# untitled.net
KiCad netlist of a schematic drawn in EAGLE
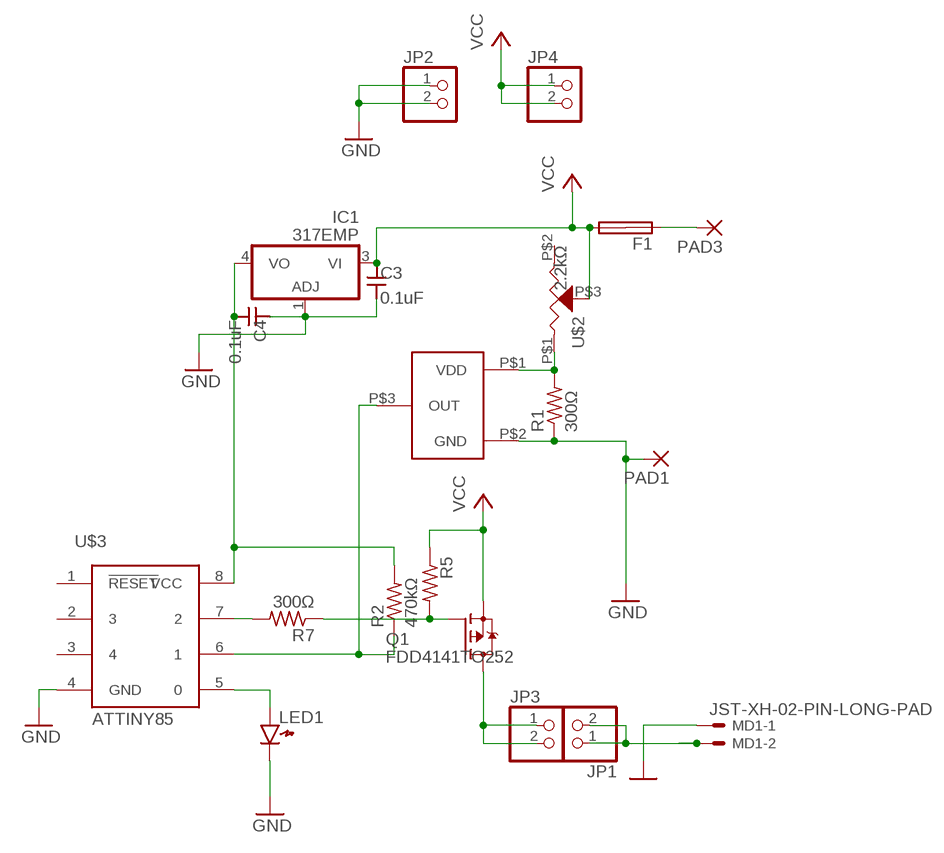
[diagram p0: schematic, sheet 1]

(export (version "E")
  (design (tool "Eeschema 10.0.6"))
  (components
    (comp (ref "C3")
      (value "0.1uF")
      (footprint "eagle-import:SMD1608")
      (libsource (lib "eagle-import") (part "CAPACITOR1608"))
    )
    (comp (ref "C4")
      (value "0.1uF")
      (footprint "eagle-import:SMD1608")
      (libsource (lib "eagle-import") (part "CAPACITOR1608"))
    )
    (comp (ref "F1")
      (value "SH32")
      (footprint "eagle-import:SH32")
      (fields (field (name "MPN") "10207101009"))
      (libsource (lib "eagle-import") (part "SH32"))
    )
    (comp (ref "IC1")
      (value "317EMP")
      (footprint "eagle-import:SOT223")
      (libsource (lib "eagle-import") (part "317EMP"))
    )
    (comp (ref "JP1")
      (value "PINHD-1X2")
      (footprint "eagle-import:1X02")
      (libsource (lib "eagle-import") (part "PINHD-1X2"))
    )
    (comp (ref "JP2")
      (value "PINHD-1X2")
      (footprint "eagle-import:1X02")
      (libsource (lib "eagle-import") (part "PINHD-1X2"))
    )
    (comp (ref "JP3")
      (value "PINHD-1X2")
      (footprint "eagle-import:1X02")
      (libsource (lib "eagle-import") (part "PINHD-1X2"))
    )
    (comp (ref "JP4")
      (value "PINHD-1X2")
      (footprint "eagle-import:1X02")
      (libsource (lib "eagle-import") (part "PINHD-1X2"))
    )
    (comp (ref "LED1")
      (value "LED1608")
      (footprint "eagle-import:LED1608")
      (libsource (lib "eagle-import") (part "LED1608"))
    )
    (comp (ref "MD1")
      (value "JST-XH-02-PIN-LONG-PAD")
      (footprint "eagle-import:JST-XH-02-PACKAGE-LONG-PAD")
      (libsource (lib "eagle-import") (part "JST-XH-02-PIN-LONG-PAD"))
    )
    (comp (ref "PAD1")
      (value "3,81/1,4")
      (footprint "eagle-import:3,81_1,4")
      (libsource (lib "eagle-import") (part "3,81/1,4"))
    )
    (comp (ref "PAD3")
      (value "3,81/1,4")
      (footprint "eagle-import:3,81_1,4")
      (libsource (lib "eagle-import") (part "3,81/1,4"))
    )
    (comp (ref "Q1")
      (value "FDD4141TO252")
      (footprint "eagle-import:TO252")
      (libsource (lib "eagle-import") (part "FDD4141TO252"))
    )
    (comp (ref "R1")
      (value "300Ω")
      (footprint "eagle-import:M2012")
      (libsource (lib "eagle-import") (part "R-US_M2012"))
    )
    (comp (ref "R2")
      (value "470kΩ")
      (footprint "eagle-import:M2012")
      (libsource (lib "eagle-import") (part "R-US_M2012"))
    )
    (comp (ref "R5")
      (value "10k")
      (footprint "eagle-import:M2012")
      (libsource (lib "eagle-import") (part "R-US_M2012"))
    )
    (comp (ref "R7")
      (value "300Ω")
      (footprint "eagle-import:M2012")
      (libsource (lib "eagle-import") (part "R-US_M2012"))
    )
    (comp (ref "U$1")
      (value "R3111N211A")
      (footprint "eagle-import:R3111N211A")
      (libsource (lib "eagle-import") (part "R3111N211A"))
    )
    (comp (ref "U$2")
      (value "2.2kΩ")
      (footprint "eagle-import:SMD-R-TRIM")
      (libsource (lib "eagle-import") (part "SMD-R-TRIM"))
    )
    (comp (ref "U$3")
      (value "ATTINY85")
      (footprint "eagle-import:8P3")
      (libsource (lib "eagle-import") (part "ATTINY85"))
    )
  )
  (nets
    (net (code "1") (name "GND") (class "Default")
      (node (ref "C3") (pin "2") (pinfunction "2_2") (pintype "passive"))
      (node (ref "C4") (pin "1") (pinfunction "1_1") (pintype "passive"))
      (node (ref "IC1") (pin "1") (pinfunction "ADJ_1") (pintype "input"))
      (node (ref "JP2") (pin "1") (pinfunction "1_1") (pintype "passive"))
      (node (ref "JP2") (pin "2") (pinfunction "2_2") (pintype "passive"))
      (node (ref "LED1") (pin "K") (pinfunction "K_K") (pintype "passive"))
      (node (ref "MD1") (pin "1") (pinfunction "S_1") (pintype "passive"))
      (node (ref "PAD1") (pin "1") (pinfunction "P_1") (pintype "passive"))
      (node (ref "R1") (pin "1") (pinfunction "1_1") (pintype "passive"))
      (node (ref "U$1") (pin "P$2") (pinfunction "GND_P$2") (pintype "bidirectional"))
      (node (ref "U$3") (pin "4") (pinfunction "GND_4") (pintype "power_in"))
    )
    (net (code "2") (name "Net-(IC1-VO)") (class "Default")
      (node (ref "C4") (pin "2") (pinfunction "2_2") (pintype "passive"))
      (node (ref "IC1") (pin "4") (pinfunction "VO_4") (pintype "passive"))
      (node (ref "R2") (pin "2") (pinfunction "2_2") (pintype "passive"))
      (node (ref "U$3") (pin "8") (pinfunction "VCC_8") (pintype "power_in"))
    )
    (net (code "3") (name "Net-(MD1B-S)") (class "Default")
      (node (ref "JP1") (pin "1") (pinfunction "1_1") (pintype "passive"))
      (node (ref "JP1") (pin "2") (pinfunction "2_2") (pintype "passive"))
      (node (ref "MD1") (pin "2") (pinfunction "S_2") (pintype "passive"))
    )
    (net (code "4") (name "Net-(PAD3-P)") (class "Default")
      (node (ref "F1") (pin "1A") (pinfunction "1A_1A") (pintype "passive"))
      (node (ref "PAD3") (pin "1") (pinfunction "P_1") (pintype "passive"))
    )
    (net (code "5") (name "Net-(Q1-D)") (class "Default")
      (node (ref "JP3") (pin "1") (pinfunction "1_1") (pintype "passive"))
      (node (ref "JP3") (pin "2") (pinfunction "2_2") (pintype "passive"))
      (node (ref "Q1") (pin "3") (pinfunction "D_3") (pintype "passive"))
    )
    (net (code "6") (name "Net-(Q1-G)") (class "Default")
      (node (ref "Q1") (pin "1") (pinfunction "G_1") (pintype "passive"))
      (node (ref "R5") (pin "2") (pinfunction "2_2") (pintype "passive"))
      (node (ref "R7") (pin "1") (pinfunction "1_1") (pintype "passive"))
    )
    (net (code "7") (name "Net-(U$1-OUT)") (class "Default")
      (node (ref "R2") (pin "1") (pinfunction "1_1") (pintype "passive"))
      (node (ref "U$1") (pin "P$3") (pinfunction "OUT_P$3") (pintype "bidirectional"))
      (node (ref "U$3") (pin "6") (pinfunction "1_6") (pintype "bidirectional"))
    )
    (net (code "8") (name "Net-(U$1-VDD)") (class "Default")
      (node (ref "R1") (pin "2") (pinfunction "2_2") (pintype "passive"))
      (node (ref "U$1") (pin "P$1") (pinfunction "VDD_P$1") (pintype "bidirectional"))
      (node (ref "U$2") (pin "P$1") (pinfunction "3_P$1") (pintype "passive"))
    )
    (net (code "9") (name "Net-(U$3-0)") (class "Default")
      (node (ref "LED1") (pin "A") (pinfunction "A_A") (pintype "passive"))
      (node (ref "U$3") (pin "5") (pinfunction "0_5") (pintype "bidirectional"))
    )
    (net (code "10") (name "Net-(U$3-2)") (class "Default")
      (node (ref "R7") (pin "2") (pinfunction "2_2") (pintype "passive"))
      (node (ref "U$3") (pin "7") (pinfunction "2_7") (pintype "bidirectional"))
    )
    (net (code "11") (name "VCC") (class "Default")
      (node (ref "C3") (pin "1") (pinfunction "1_1") (pintype "passive"))
      (node (ref "F1") (pin "2A") (pinfunction "2A_2A") (pintype "passive"))
      (node (ref "IC1") (pin "3") (pinfunction "VI_3") (pintype "input"))
      (node (ref "JP4") (pin "1") (pinfunction "1_1") (pintype "passive"))
      (node (ref "JP4") (pin "2") (pinfunction "2_2") (pintype "passive"))
      (node (ref "Q1") (pin "2") (pinfunction "S_2") (pintype "passive"))
      (node (ref "R5") (pin "1") (pinfunction "1_1") (pintype "passive"))
      (node (ref "U$2") (pin "P$3") (pinfunction "2_P$3") (pintype "passive"))
    )
    (net (code "12") (name "unconnected-(F1-Pad1B)") (class "Default")
      (node (ref "F1") (pin "1B") (pinfunction "1B_1B") (pintype "passive"))
    )
    (net (code "13") (name "unconnected-(F1-Pad2B)") (class "Default")
      (node (ref "F1") (pin "2B") (pinfunction "2B_2B") (pintype "passive"))
    )
    (net (code "14") (name "unconnected-(U$2-1-PadP$2)") (class "Default")
      (node (ref "U$2") (pin "P$2") (pinfunction "1_P$2") (pintype "passive"))
    )
    (net (code "15") (name "unconnected-(U$3-3-Pad2)") (class "Default")
      (node (ref "U$3") (pin "2") (pinfunction "3_2") (pintype "bidirectional"))
    )
    (net (code "16") (name "unconnected-(U$3-4-Pad3)") (class "Default")
      (node (ref "U$3") (pin "3") (pinfunction "4_3") (pintype "bidirectional"))
    )
    (net (code "17") (name "unconnected-(U$3-~{RESET}-Pad1)") (class "Default")
      (node (ref "U$3") (pin "1") (pinfunction "~{RESET}_1") (pintype "bidirectional"))
    )
  )
)
